# dac2b-only.net
KiCad netlist of a schematic drawn in EAGLE
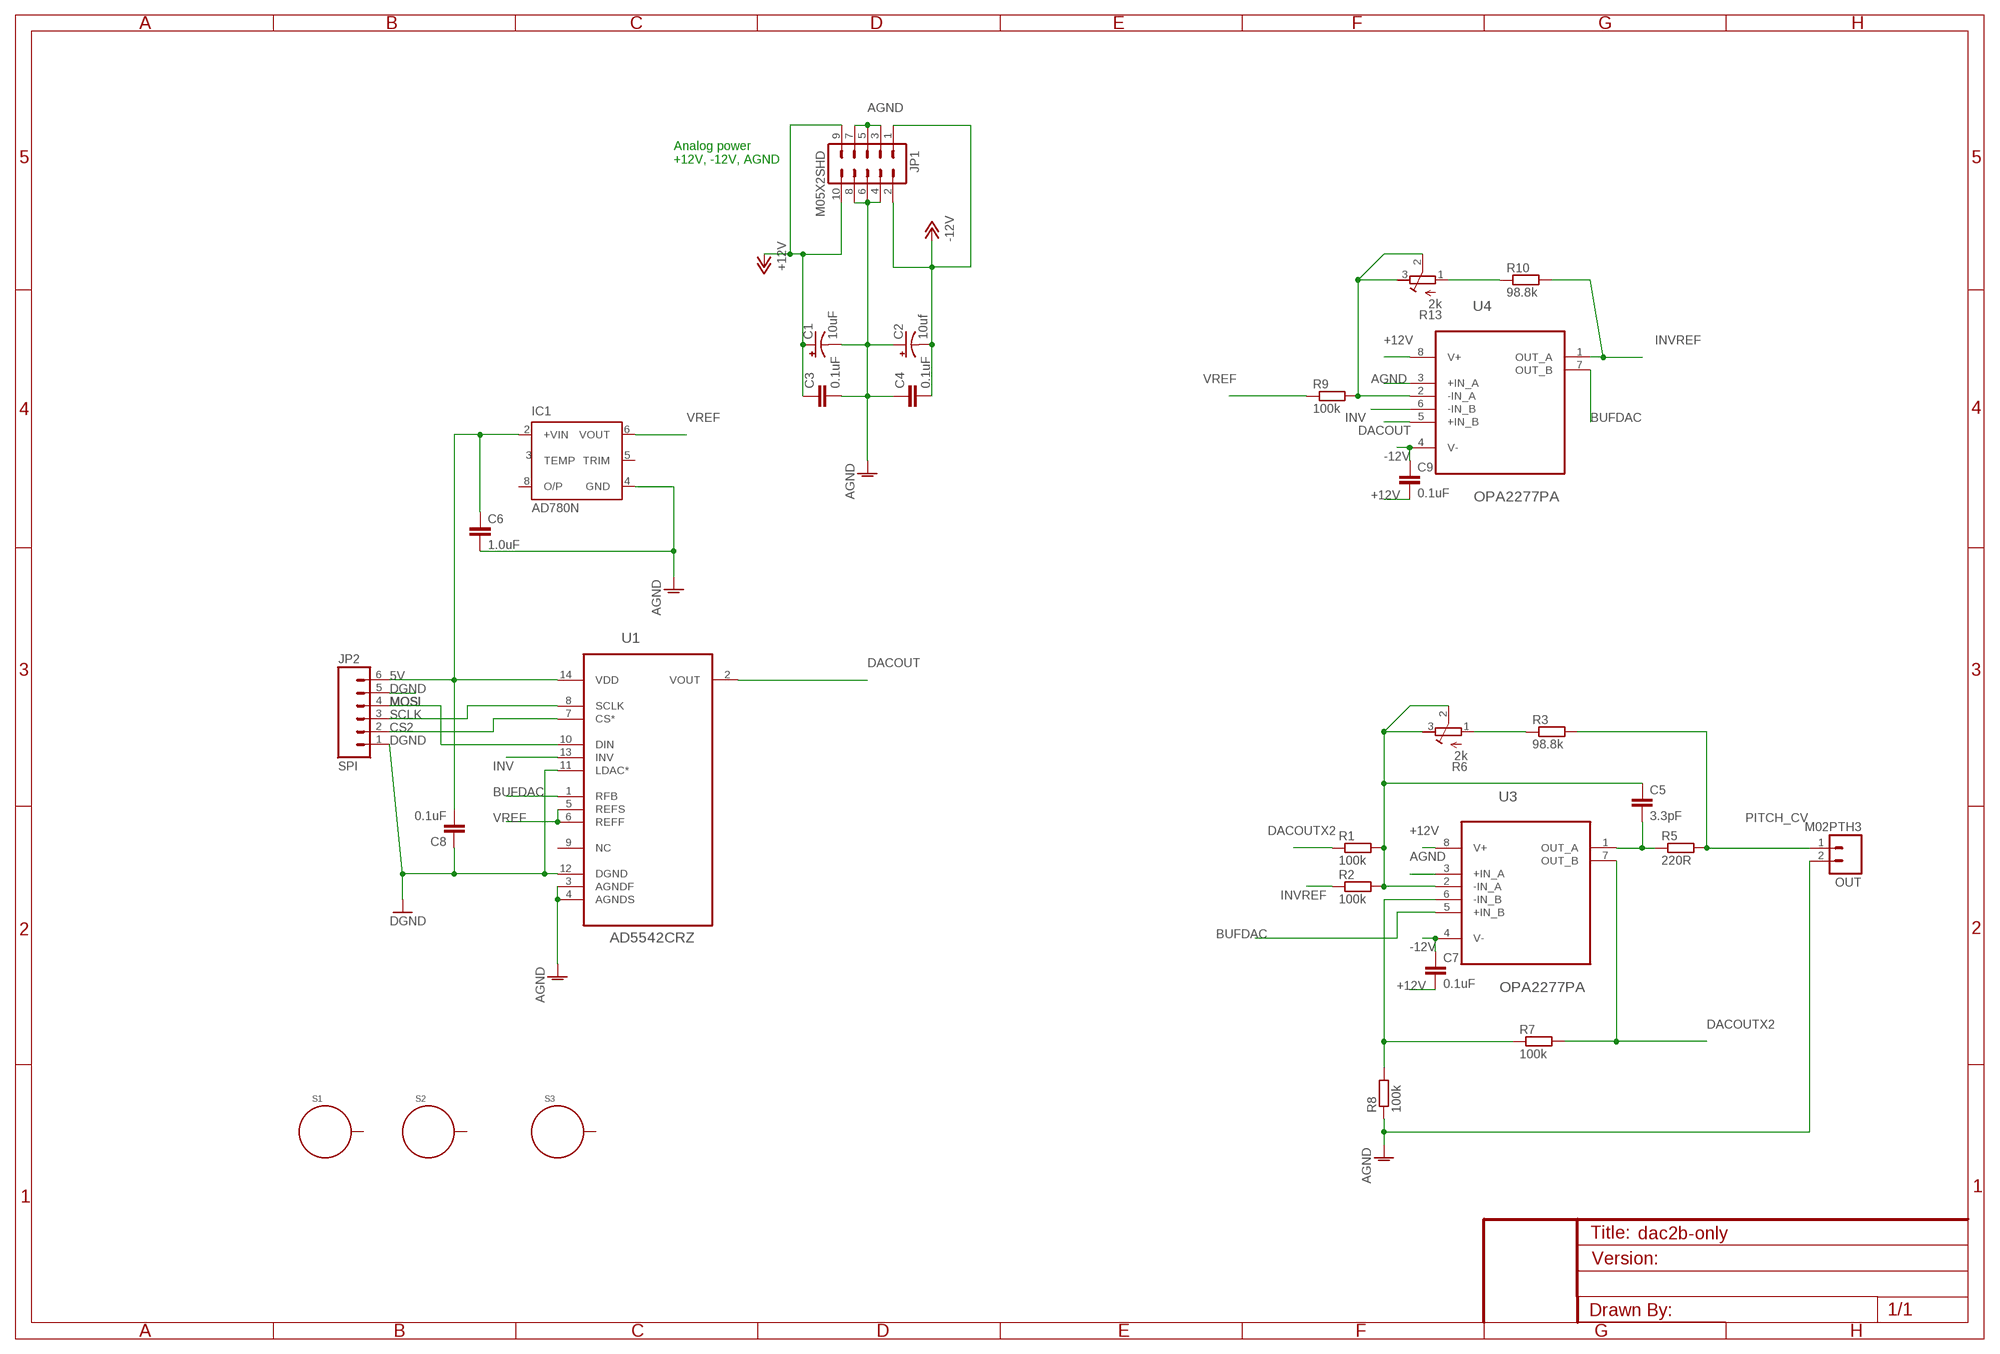
[diagram p0: schematic, sheet 1]

(export (version "E")
  (design (tool "Eeschema 10.0.6"))
  (components
    (comp (ref "C1")
      (value "10uF")
      (footprint "eagle-import:CPOL-RADIAL-100UF-25V")
      (libsource (lib "eagle-import") (part "CAP_POLPTH1"))
    )
    (comp (ref "C2")
      (value "10uf")
      (footprint "eagle-import:CPOL-RADIAL-100UF-25V")
      (libsource (lib "eagle-import") (part "CAP_POLPTH1"))
    )
    (comp (ref "C3")
      (value "0.1uF")
      (footprint "eagle-import:C050-055X075")
      (libsource (lib "eagle-import") (part "resistor_C-EU050-055X075"))
    )
    (comp (ref "C4")
      (value "0.1uF")
      (footprint "eagle-import:C050-055X075")
      (libsource (lib "eagle-import") (part "resistor_C-EU050-055X075"))
    )
    (comp (ref "C5")
      (value "3.3pF")
      (footprint "eagle-import:C025-025X050")
      (libsource (lib "eagle-import") (part "resistor_C-EU025-025X050"))
    )
    (comp (ref "C6")
      (value "1.0uF")
      (footprint "eagle-import:C075-032X103")
      (libsource (lib "eagle-import") (part "C-EU075-032X103"))
    )
    (comp (ref "C7")
      (value "0.1uF")
      (footprint "eagle-import:C025-025X050")
      (libsource (lib "eagle-import") (part "resistor_C-EU025-025X050"))
    )
    (comp (ref "C8")
      (value "0.1uF")
      (footprint "eagle-import:C050-055X075")
      (libsource (lib "eagle-import") (part "resistor_C-EU050-055X075"))
    )
    (comp (ref "C9")
      (value "0.1uF")
      (footprint "eagle-import:C025-025X050")
      (libsource (lib "eagle-import") (part "resistor_C-EU025-025X050"))
    )
    (comp (ref "IC1")
      (value "AD780N")
      (footprint "eagle-import:DIL08")
      (libsource (lib "eagle-import") (part "AD780N"))
    )
    (comp (ref "JP1")
      (value "M05X2SHD")
      (footprint "eagle-import:2X5-SHROUDED")
      (libsource (lib "eagle-import") (part "M05X2SHD"))
    )
    (comp (ref "JP2")
      (value "SPI")
      (footprint "eagle-import:1X06")
      (libsource (lib "eagle-import") (part "M06SIP"))
    )
    (comp (ref "OUT")
      (value "M02PTH3")
      (footprint "eagle-import:1X02_LONGPADS")
      (libsource (lib "eagle-import") (part "M02PTH3"))
    )
    (comp (ref "R1")
      (value "100k")
      (footprint "eagle-import:0207_10")
      (libsource (lib "eagle-import") (part "R-EU_0207/10"))
    )
    (comp (ref "R2")
      (value "100k")
      (footprint "eagle-import:0207_10")
      (libsource (lib "eagle-import") (part "R-EU_0207/10"))
    )
    (comp (ref "R3")
      (value "98.8k")
      (footprint "eagle-import:0207_10")
      (libsource (lib "eagle-import") (part "R-EU_0207/10"))
    )
    (comp (ref "R5")
      (value "220R")
      (footprint "eagle-import:0207_10")
      (libsource (lib "eagle-import") (part "R-EU_0207/10"))
    )
    (comp (ref "R6")
      (value "2k")
      (footprint "eagle-import:RTRIM3296W")
      (libsource (lib "eagle-import") (part "R-TRIMM3296W"))
    )
    (comp (ref "R7")
      (value "100k")
      (footprint "eagle-import:0207_10")
      (libsource (lib "eagle-import") (part "R-EU_0207/10"))
    )
    (comp (ref "R8")
      (value "100k")
      (footprint "eagle-import:0207_10")
      (libsource (lib "eagle-import") (part "R-EU_0207/10"))
    )
    (comp (ref "R9")
      (value "100k")
      (footprint "eagle-import:0207_10")
      (libsource (lib "eagle-import") (part "R-EU_0207/10"))
    )
    (comp (ref "R10")
      (value "98.8k")
      (footprint "eagle-import:0207_10")
      (libsource (lib "eagle-import") (part "R-EU_0207/10"))
    )
    (comp (ref "R13")
      (value "2k")
      (footprint "eagle-import:RTRIM3296W")
      (libsource (lib "eagle-import") (part "R-TRIMM3296W"))
    )
    (comp (ref "S1")
      (value "STANDOFF_ELECTRICAL")
      (footprint "eagle-import:STANDOFF-ELECTRICAL")
      (libsource (lib "eagle-import") (part "STANDOFF_ELECTRICAL"))
    )
    (comp (ref "S2")
      (value "STANDOFF_ELECTRICAL")
      (footprint "eagle-import:STANDOFF-ELECTRICAL")
      (libsource (lib "eagle-import") (part "STANDOFF_ELECTRICAL"))
    )
    (comp (ref "S3")
      (value "STANDOFF_ELECTRICAL")
      (footprint "eagle-import:STANDOFF-ELECTRICAL")
      (libsource (lib "eagle-import") (part "STANDOFF_ELECTRICAL"))
    )
    (comp (ref "U1")
      (value "AD5542CRZ")
      (footprint "eagle-import:SOIC127P600X175-14N")
      (libsource (lib "eagle-import") (part "AD5542CRZ"))
    )
    (comp (ref "U3")
      (value "OPA2277PA")
      (footprint "eagle-import:DIP254P762X508-8")
      (libsource (lib "eagle-import") (part "OPA2277PA"))
    )
    (comp (ref "U4")
      (value "OPA2277PA")
      (footprint "eagle-import:DIP254P762X508-8")
      (libsource (lib "eagle-import") (part "OPA2277PA"))
    )
  )
  (nets
    (net (code "1") (name "+12V") (class "Default")
      (node (ref "C1") (pin "1") (pinfunction "+_1") (pintype "passive"))
      (node (ref "C3") (pin "1") (pinfunction "1_1") (pintype "passive"))
      (node (ref "C7") (pin "2") (pinfunction "2_2") (pintype "passive"))
      (node (ref "C9") (pin "2") (pinfunction "2_2") (pintype "passive"))
      (node (ref "JP1") (pin "10") (pinfunction "10_10") (pintype "passive"))
      (node (ref "JP1") (pin "9") (pinfunction "9_9") (pintype "passive"))
      (node (ref "U3") (pin "8") (pinfunction "V+_8") (pintype "power_in"))
      (node (ref "U4") (pin "8") (pinfunction "V+_8") (pintype "power_in"))
    )
    (net (code "2") (name "-12V") (class "Default")
      (node (ref "C2") (pin "2") (pinfunction "-_2") (pintype "passive"))
      (node (ref "C4") (pin "2") (pinfunction "2_2") (pintype "passive"))
      (node (ref "C7") (pin "1") (pinfunction "1_1") (pintype "passive"))
      (node (ref "C9") (pin "1") (pinfunction "1_1") (pintype "passive"))
      (node (ref "JP1") (pin "1") (pinfunction "1_1") (pintype "passive"))
      (node (ref "JP1") (pin "2") (pinfunction "2_2") (pintype "passive"))
      (node (ref "U3") (pin "4") (pinfunction "V-_4") (pintype "power_in"))
      (node (ref "U4") (pin "4") (pinfunction "V-_4") (pintype "power_in"))
    )
    (net (code "3") (name "/5V") (class "Default")
      (node (ref "C6") (pin "1") (pinfunction "1_1") (pintype "passive"))
      (node (ref "C8") (pin "2") (pinfunction "2_2") (pintype "passive"))
      (node (ref "IC1") (pin "2") (pinfunction "+VIN_2") (pintype "input"))
      (node (ref "JP2") (pin "6") (pinfunction "6_6") (pintype "passive"))
      (node (ref "U1") (pin "14") (pinfunction "VDD_14") (pintype "power_in"))
    )
    (net (code "4") (name "/BUFDAC") (class "Default")
      (node (ref "U1") (pin "1") (pinfunction "RFB_1") (pintype "passive"))
      (node (ref "U3") (pin "5") (pinfunction "+IN_B_5") (pintype "input"))
      (node (ref "U4") (pin "7") (pinfunction "OUT_B_7") (pintype "output"))
    )
    (net (code "5") (name "/CS2") (class "Default")
      (node (ref "JP2") (pin "2") (pinfunction "2_2") (pintype "passive"))
      (node (ref "U1") (pin "7") (pinfunction "CS*_7") (pintype "input"))
    )
    (net (code "6") (name "/DACOUT") (class "Default")
      (node (ref "U1") (pin "2") (pinfunction "VOUT_2") (pintype "output"))
      (node (ref "U4") (pin "5") (pinfunction "+IN_B_5") (pintype "input"))
    )
    (net (code "7") (name "/DACOUTX2") (class "Default")
      (node (ref "R1") (pin "1") (pinfunction "1_1") (pintype "passive"))
      (node (ref "R7") (pin "2") (pinfunction "2_2") (pintype "passive"))
      (node (ref "U3") (pin "7") (pinfunction "OUT_B_7") (pintype "output"))
    )
    (net (code "8") (name "/INV") (class "Default")
      (node (ref "U1") (pin "13") (pinfunction "INV_13") (pintype "passive"))
      (node (ref "U4") (pin "6") (pinfunction "-IN_B_6") (pintype "input"))
    )
    (net (code "9") (name "/INVREF") (class "Default")
      (node (ref "R10") (pin "2") (pinfunction "2_2") (pintype "passive"))
      (node (ref "R2") (pin "1") (pinfunction "1_1") (pintype "passive"))
      (node (ref "U4") (pin "1") (pinfunction "OUT_A_1") (pintype "output"))
    )
    (net (code "10") (name "/MOSI") (class "Default")
      (node (ref "JP2") (pin "4") (pinfunction "4_4") (pintype "passive"))
      (node (ref "U1") (pin "10") (pinfunction "DIN_10") (pintype "input"))
    )
    (net (code "11") (name "/PITCH_CV") (class "Default")
      (node (ref "OUT") (pin "1") (pinfunction "1_1") (pintype "passive"))
      (node (ref "R3") (pin "2") (pinfunction "2_2") (pintype "passive"))
      (node (ref "R5") (pin "2") (pinfunction "2_2") (pintype "passive"))
    )
    (net (code "12") (name "/SCLK") (class "Default")
      (node (ref "JP2") (pin "3") (pinfunction "3_3") (pintype "passive"))
      (node (ref "U1") (pin "8") (pinfunction "SCLK_8") (pintype "input"))
    )
    (net (code "13") (name "/VREF") (class "Default")
      (node (ref "IC1") (pin "6") (pinfunction "VOUT_6") (pintype "input"))
      (node (ref "R9") (pin "1") (pinfunction "1_1") (pintype "passive"))
      (node (ref "U1") (pin "5") (pinfunction "REFS_5") (pintype "input"))
      (node (ref "U1") (pin "6") (pinfunction "REFF_6") (pintype "input"))
    )
    (net (code "14") (name "AGND") (class "Default")
      (node (ref "C1") (pin "2") (pinfunction "-_2") (pintype "passive"))
      (node (ref "C2") (pin "1") (pinfunction "+_1") (pintype "passive"))
      (node (ref "C3") (pin "2") (pinfunction "2_2") (pintype "passive"))
      (node (ref "C4") (pin "1") (pinfunction "1_1") (pintype "passive"))
      (node (ref "C6") (pin "2") (pinfunction "2_2") (pintype "passive"))
      (node (ref "IC1") (pin "4") (pinfunction "GND_4") (pintype "power_in"))
      (node (ref "JP1") (pin "3") (pinfunction "3_3") (pintype "passive"))
      (node (ref "JP1") (pin "4") (pinfunction "4_4") (pintype "passive"))
      (node (ref "JP1") (pin "5") (pinfunction "5_5") (pintype "passive"))
      (node (ref "JP1") (pin "6") (pinfunction "6_6") (pintype "passive"))
      (node (ref "JP1") (pin "7") (pinfunction "7_7") (pintype "passive"))
      (node (ref "JP1") (pin "8") (pinfunction "8_8") (pintype "passive"))
      (node (ref "OUT") (pin "2") (pinfunction "2_2") (pintype "passive"))
      (node (ref "R8") (pin "1") (pinfunction "1_1") (pintype "passive"))
      (node (ref "U1") (pin "3") (pinfunction "AGNDF_3") (pintype "passive"))
      (node (ref "U1") (pin "4") (pinfunction "AGNDS_4") (pintype "passive"))
      (node (ref "U3") (pin "3") (pinfunction "+IN_A_3") (pintype "input"))
      (node (ref "U4") (pin "3") (pinfunction "+IN_A_3") (pintype "input"))
    )
    (net (code "15") (name "DGND") (class "Default")
      (node (ref "C8") (pin "1") (pinfunction "1_1") (pintype "passive"))
      (node (ref "JP2") (pin "1") (pinfunction "1_1") (pintype "passive"))
      (node (ref "JP2") (pin "5") (pinfunction "5_5") (pintype "passive"))
      (node (ref "U1") (pin "11") (pinfunction "LDAC*_11") (pintype "input"))
      (node (ref "U1") (pin "12") (pinfunction "DGND_12") (pintype "passive"))
    )
    (net (code "16") (name "Net-(R6-A)") (class "Default")
      (node (ref "C5") (pin "1") (pinfunction "1_1") (pintype "passive"))
      (node (ref "R1") (pin "2") (pinfunction "2_2") (pintype "passive"))
      (node (ref "R2") (pin "2") (pinfunction "2_2") (pintype "passive"))
      (node (ref "R6") (pin "2") (pinfunction "S_2") (pintype "passive"))
      (node (ref "R6") (pin "3") (pinfunction "A_3") (pintype "passive"))
      (node (ref "U3") (pin "2") (pinfunction "-IN_A_2") (pintype "input"))
    )
    (net (code "17") (name "Net-(R6-E)") (class "Default")
      (node (ref "R3") (pin "1") (pinfunction "1_1") (pintype "passive"))
      (node (ref "R6") (pin "1") (pinfunction "E_1") (pintype "passive"))
    )
    (net (code "18") (name "Net-(R13-A)") (class "Default")
      (node (ref "R13") (pin "2") (pinfunction "S_2") (pintype "passive"))
      (node (ref "R13") (pin "3") (pinfunction "A_3") (pintype "passive"))
      (node (ref "R9") (pin "2") (pinfunction "2_2") (pintype "passive"))
      (node (ref "U4") (pin "2") (pinfunction "-IN_A_2") (pintype "input"))
    )
    (net (code "19") (name "Net-(R13-E)") (class "Default")
      (node (ref "R10") (pin "1") (pinfunction "1_1") (pintype "passive"))
      (node (ref "R13") (pin "1") (pinfunction "E_1") (pintype "passive"))
    )
    (net (code "20") (name "Net-(U3--IN_B)") (class "Default")
      (node (ref "R7") (pin "1") (pinfunction "1_1") (pintype "passive"))
      (node (ref "R8") (pin "2") (pinfunction "2_2") (pintype "passive"))
      (node (ref "U3") (pin "6") (pinfunction "-IN_B_6") (pintype "input"))
    )
    (net (code "21") (name "Net-(U3-OUT_A)") (class "Default")
      (node (ref "C5") (pin "2") (pinfunction "2_2") (pintype "passive"))
      (node (ref "R5") (pin "1") (pinfunction "1_1") (pintype "passive"))
      (node (ref "U3") (pin "1") (pinfunction "OUT_A_1") (pintype "output"))
    )
    (net (code "22") (name "unconnected-(IC1-O{slash}P-Pad8)") (class "Default")
      (node (ref "IC1") (pin "8") (pinfunction "O/P_8") (pintype "passive"))
    )
    (net (code "23") (name "unconnected-(IC1-TEMP-Pad3)") (class "Default")
      (node (ref "IC1") (pin "3") (pinfunction "TEMP_3") (pintype "input"))
    )
    (net (code "24") (name "unconnected-(IC1-TRIM-Pad5)") (class "Default")
      (node (ref "IC1") (pin "5") (pinfunction "TRIM_5") (pintype "input"))
    )
    (net (code "25") (name "unconnected-(S1-P$1-PadP1)") (class "Default")
      (node (ref "S1") (pin "P1") (pinfunction "P$1_P1") (pintype "bidirectional"))
    )
    (net (code "26") (name "unconnected-(S2-P$1-PadP1)") (class "Default")
      (node (ref "S2") (pin "P1") (pinfunction "P$1_P1") (pintype "bidirectional"))
    )
    (net (code "27") (name "unconnected-(S3-P$1-PadP1)") (class "Default")
      (node (ref "S3") (pin "P1") (pinfunction "P$1_P1") (pintype "bidirectional"))
    )
    (net (code "28") (name "unconnected-(U1-NC-Pad9)") (class "Default")
      (node (ref "U1") (pin "9") (pinfunction "NC_9") (pintype "no_connect"))
    )
  )
)
